# MCU.net
KiCad netlist of a schematic drawn in Altium Designer
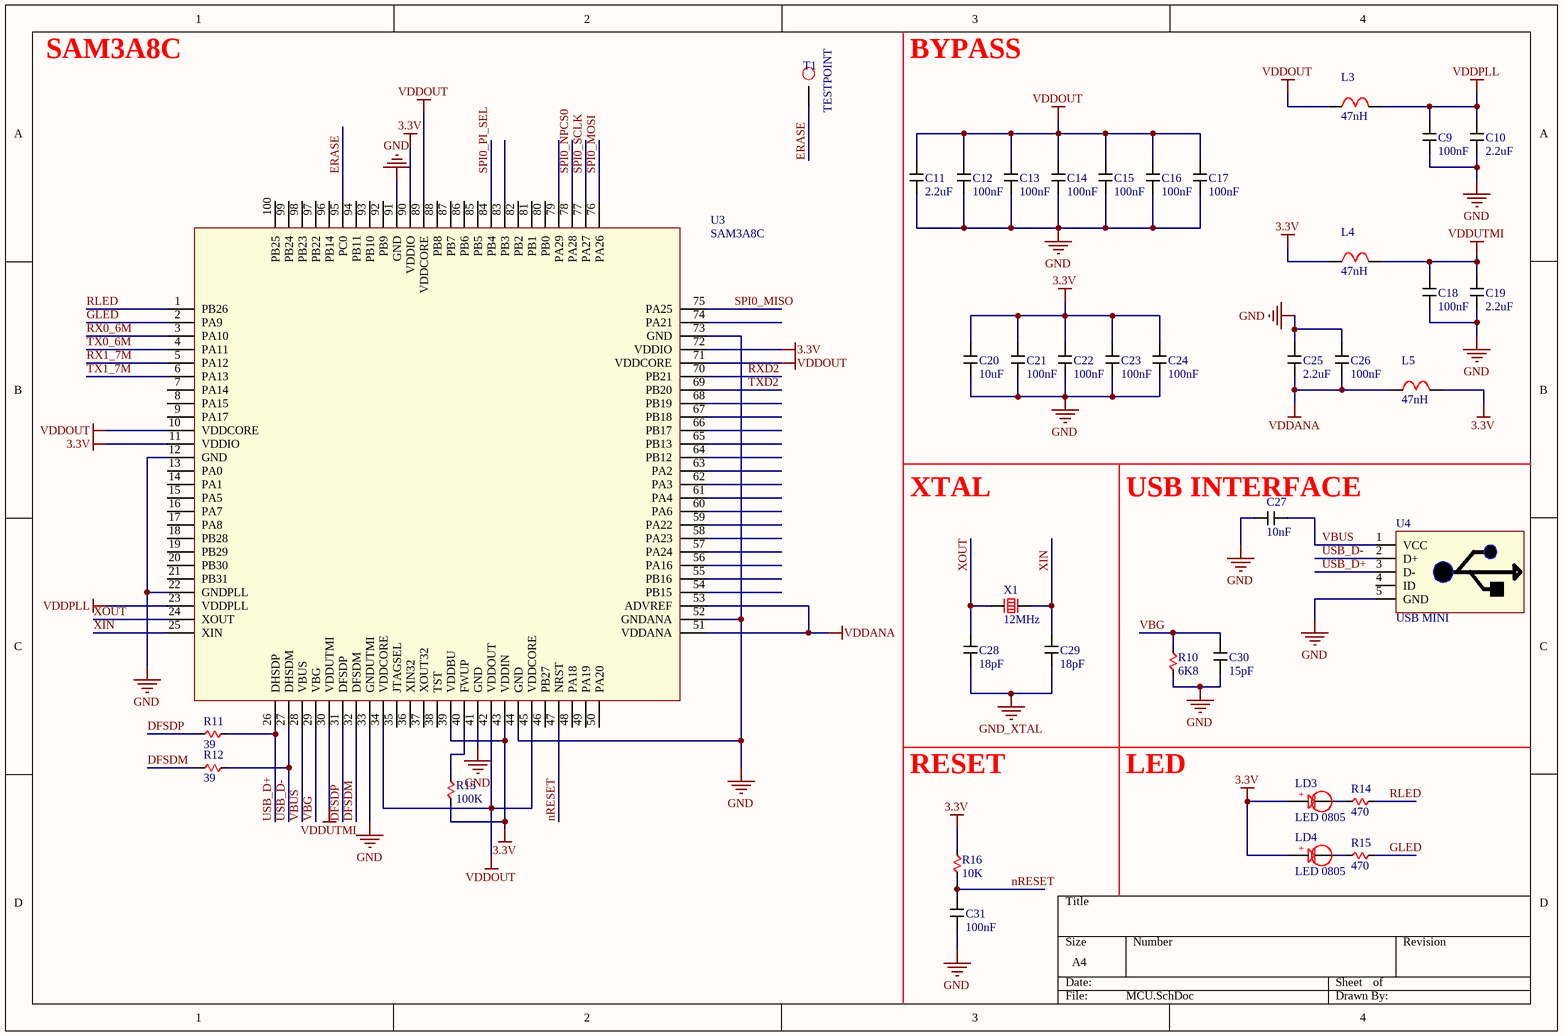
[diagram p0: MCU.SchDoc]

(export (version "E")
  (design (tool "Eeschema 10.0.6"))
  (components
    (comp (ref "C9") (value "100nF") (footprint "C 0805") (libsource (lib "SkyWar") (part "C 0805")))
    (comp (ref "C10") (value "2.2uF") (footprint "C 0805") (libsource (lib "SkyWar") (part "C 0805")))
    (comp (ref "C11") (value "2.2uF") (footprint "C 0805") (libsource (lib "SkyWar") (part "C 0805")))
    (comp (ref "C12") (value "100nF") (footprint "C 0805") (libsource (lib "SkyWar") (part "C 0805")))
    (comp (ref "C13") (value "100nF") (footprint "C 0805") (libsource (lib "SkyWar") (part "C 0805")))
    (comp (ref "C14") (value "100nF") (footprint "C 0805") (libsource (lib "SkyWar") (part "C 0805")))
    (comp (ref "C15") (value "100nF") (footprint "C 0805") (libsource (lib "SkyWar") (part "C 0805")))
    (comp (ref "C16") (value "100nF") (footprint "C 0805") (libsource (lib "SkyWar") (part "C 0805")))
    (comp (ref "C17") (value "100nF") (footprint "C 0805") (libsource (lib "SkyWar") (part "C 0805")))
    (comp (ref "C18") (value "100nF") (footprint "C 0805") (libsource (lib "SkyWar") (part "C 0805")))
    (comp (ref "C19") (value "2.2uF") (footprint "C 0805") (libsource (lib "SkyWar") (part "C 0805")))
    (comp (ref "C20") (value "10uF") (footprint "C 0805") (libsource (lib "SkyWar") (part "C 0805")))
    (comp (ref "C21") (value "100nF") (footprint "C 0805") (libsource (lib "SkyWar") (part "C 0805")))
    (comp (ref "C22") (value "100nF") (footprint "C 0805") (libsource (lib "SkyWar") (part "C 0805")))
    (comp (ref "C23") (value "100nF") (footprint "C 0805") (libsource (lib "SkyWar") (part "C 0805")))
    (comp (ref "C24") (value "100nF") (footprint "C 0805") (libsource (lib "SkyWar") (part "C 0805")))
    (comp (ref "C25") (value "2.2uF") (footprint "C 0805") (libsource (lib "SkyWar") (part "C 0805")))
    (comp (ref "C26") (value "100nF") (footprint "C 0805") (libsource (lib "SkyWar") (part "C 0805")))
    (comp (ref "C27") (value "10nF") (footprint "C 0805") (libsource (lib "SkyWar") (part "C 0805")))
    (comp (ref "C28") (value "18pF") (footprint "C 0805") (libsource (lib "SkyWar") (part "C 0805")))
    (comp (ref "C29") (value "18pF") (footprint "C 0805") (libsource (lib "SkyWar") (part "C 0805")))
    (comp (ref "C30") (value "15pF") (footprint "C 0805") (libsource (lib "SkyWar") (part "C 0805")))
    (comp (ref "C31") (value "100nF") (footprint "C 0805") (libsource (lib "SkyWar") (part "C 0805")))
    (comp (ref "L3") (value "47nH") (footprint "L 0805") (libsource (lib "SkyWar") (part "L 0805")))
    (comp (ref "L4") (value "47nH") (footprint "L 0805") (libsource (lib "SkyWar") (part "L 0805")))
    (comp (ref "L5") (value "47nH") (footprint "L 0805") (libsource (lib "SkyWar") (part "L 0805")))
    (comp (ref "LD3") (value "LED 0805") (footprint "LED 0805") (libsource (lib "SkyWar") (part "LED 0805")))
    (comp (ref "LD4") (value "LED 0805") (footprint "LED 0805") (libsource (lib "SkyWar") (part "LED 0805")))
    (comp (ref "R10") (value "6K8") (footprint "R 0805") (libsource (lib "SkyWar") (part "R 0805")))
    (comp (ref "R11") (value "39") (footprint "R 0805") (libsource (lib "SkyWar") (part "R 0805")))
    (comp (ref "R12") (value "39") (footprint "R 0805") (libsource (lib "SkyWar") (part "R 0805")))
    (comp (ref "R13") (value "100K") (footprint "R 0805") (libsource (lib "SkyWar") (part "R 0805")))
    (comp (ref "R14") (value "470") (footprint "R 0805") (libsource (lib "SkyWar") (part "R 0805")))
    (comp (ref "R15") (value "470") (footprint "R 0805") (libsource (lib "SkyWar") (part "R 0805")))
    (comp (ref "R16") (value "10K") (footprint "R 0805") (libsource (lib "SkyWar") (part "R 0805")))
    (comp (ref "T1")
      (value "TESTPOINT")
      (footprint "TEST_POINT")
      (libsource (lib "SkyWar") (part "TEST_POINT"))
    )
    (comp (ref "U3") (value "SAM3A8C") (footprint "SAM3A8C") (libsource (lib "SkyWar") (part "SAM3A8C")))
    (comp (ref "U4")
      (value "USB MINI")
      (footprint "USB MINI DIP")
      (libsource (lib "SkyWar") (part "USB TYPE B"))
    )
    (comp (ref "X1") (value "12MHz") (footprint "XTAL") (libsource (lib "SkyWar") (part "XTAL")))
  )
  (nets
    (net (code "1") (name "/DFSDM") (class "Default")
      (node (ref "R12") (pin "1") (pinfunction "0_1") (pintype "passive"))
      (node (ref "U3") (pin "32") (pinfunction "DFSDM_32") (pintype "passive"))
    )
    (net (code "2") (name "/DFSDP") (class "Default")
      (node (ref "R11") (pin "1") (pinfunction "0_1") (pintype "passive"))
      (node (ref "U3") (pin "31") (pinfunction "DFSDP_31") (pintype "passive"))
    )
    (net (code "3") (name "/ERASE") (class "Default")
      (node (ref "T1") (pin "1") (pintype "passive"))
      (node (ref "U3") (pin "95") (pinfunction "PC0_95") (pintype "passive"))
    )
    (net (code "4") (name "/GLED") (class "Default")
      (node (ref "R15") (pin "1") (pinfunction "0_1") (pintype "passive"))
      (node (ref "U3") (pin "2") (pinfunction "PA9_2") (pintype "passive"))
    )
    (net (code "5") (name "/RLED") (class "Default")
      (node (ref "R14") (pin "1") (pinfunction "0_1") (pintype "passive"))
      (node (ref "U3") (pin "1") (pinfunction "PB26_1") (pintype "passive"))
    )
    (net (code "6") (name "/RX0_6M") (class "Default")
      (node (ref "U3") (pin "3") (pinfunction "PA10_3") (pintype "passive"))
    )
    (net (code "7") (name "/RX1_7M") (class "Default")
      (node (ref "U3") (pin "5") (pinfunction "PA12_5") (pintype "passive"))
    )
    (net (code "8") (name "/RXD2") (class "Default")
      (node (ref "U3") (pin "70") (pinfunction "PB21_70") (pintype "passive"))
    )
    (net (code "9") (name "/SPI0_MISO") (class "Default")
      (node (ref "U3") (pin "75") (pinfunction "PA25_75") (pintype "passive"))
    )
    (net (code "10") (name "/SPI0_MOSI") (class "Default")
      (node (ref "U3") (pin "76") (pinfunction "PA26_76") (pintype "passive"))
    )
    (net (code "11") (name "/SPI0_NPCS0") (class "Default")
      (node (ref "U3") (pin "78") (pinfunction "PA28_78") (pintype "passive"))
    )
    (net (code "12") (name "/SPI0_PI_SEL") (class "Default")
      (node (ref "U3") (pin "84") (pinfunction "PB4_84") (pintype "passive"))
    )
    (net (code "13") (name "/SPI0_SCLK") (class "Default")
      (node (ref "U3") (pin "77") (pinfunction "PA27_77") (pintype "passive"))
    )
    (net (code "14") (name "/TX0_6M") (class "Default")
      (node (ref "U3") (pin "4") (pinfunction "PA11_4") (pintype "passive"))
    )
    (net (code "15") (name "/TX1_7M") (class "Default")
      (node (ref "U3") (pin "6") (pinfunction "PA13_6") (pintype "passive"))
    )
    (net (code "16") (name "/TXD2") (class "Default")
      (node (ref "U3") (pin "69") (pinfunction "PB20_69") (pintype "passive"))
    )
    (net (code "17") (name "/USB_D+") (class "Default")
      (node (ref "R11") (pin "2") (pinfunction "1_2") (pintype "passive"))
      (node (ref "U3") (pin "26") (pinfunction "DHSDP_26") (pintype "passive"))
      (node (ref "U4") (pin "3") (pinfunction "D-_3") (pintype "passive"))
    )
    (net (code "18") (name "/USB_D-") (class "Default")
      (node (ref "R12") (pin "2") (pinfunction "1_2") (pintype "passive"))
      (node (ref "U3") (pin "27") (pinfunction "DHSDM_27") (pintype "passive"))
      (node (ref "U4") (pin "2") (pinfunction "D+_2") (pintype "passive"))
    )
    (net (code "19") (name "/VBG") (class "Default")
      (node (ref "C30") (pin "2") (pintype "passive"))
      (node (ref "R10") (pin "2") (pinfunction "1_2") (pintype "passive"))
      (node (ref "U3") (pin "29") (pinfunction "VBG_29") (pintype "passive"))
    )
    (net (code "20") (name "/VBUS") (class "Default")
      (node (ref "C27") (pin "1") (pintype "passive"))
      (node (ref "U3") (pin "28") (pinfunction "VBUS_28") (pintype "passive"))
      (node (ref "U4") (pin "1") (pinfunction "VCC_1") (pintype "passive"))
    )
    (net (code "21") (name "/XIN") (class "Default")
      (node (ref "C29") (pin "2") (pintype "passive"))
      (node (ref "U3") (pin "25") (pinfunction "XIN_25") (pintype "passive"))
      (node (ref "X1") (pin "2") (pinfunction "6_2") (pintype "passive"))
    )
    (net (code "22") (name "/XOUT") (class "Default")
      (node (ref "C28") (pin "2") (pintype "passive"))
      (node (ref "U3") (pin "24") (pinfunction "XOUT_24") (pintype "passive"))
      (node (ref "X1") (pin "1") (pinfunction "5_1") (pintype "passive"))
    )
    (net (code "23") (name "/nRESET") (class "Default")
      (node (ref "C31") (pin "2") (pintype "passive"))
      (node (ref "R16") (pin "1") (pinfunction "0_1") (pintype "passive"))
      (node (ref "U3") (pin "47") (pinfunction "NRST_47") (pintype "passive"))
    )
    (net (code "24") (name "3.3V") (class "Default")
      (node (ref "C20") (pin "2") (pintype "passive"))
      (node (ref "C21") (pin "2") (pintype "passive"))
      (node (ref "C22") (pin "2") (pintype "passive"))
      (node (ref "C23") (pin "2") (pintype "passive"))
      (node (ref "C24") (pin "2") (pintype "passive"))
      (node (ref "L4") (pin "1") (pintype "passive"))
      (node (ref "L5") (pin "1") (pintype "passive"))
      (node (ref "LD3") (pin "1") (pinfunction "3_1") (pintype "passive"))
      (node (ref "LD4") (pin "1") (pinfunction "3_1") (pintype "passive"))
      (node (ref "R13") (pin "1") (pinfunction "0_1") (pintype "passive"))
      (node (ref "R16") (pin "2") (pinfunction "1_2") (pintype "passive"))
      (node (ref "U3") (pin "11") (pinfunction "VDDIO_11") (pintype "passive"))
      (node (ref "U3") (pin "39") (pinfunction "VDDBU_39") (pintype "passive"))
      (node (ref "U3") (pin "43") (pinfunction "VDDIN_43") (pintype "passive"))
      (node (ref "U3") (pin "72") (pinfunction "VDDIO_72") (pintype "passive"))
      (node (ref "U3") (pin "90") (pinfunction "VDDIO_90") (pintype "passive"))
    )
    (net (code "25") (name "GND") (class "Default")
      (node (ref "C10") (pin "1") (pintype "passive"))
      (node (ref "C11") (pin "1") (pintype "passive"))
      (node (ref "C12") (pin "1") (pintype "passive"))
      (node (ref "C13") (pin "1") (pintype "passive"))
      (node (ref "C14") (pin "1") (pintype "passive"))
      (node (ref "C15") (pin "1") (pintype "passive"))
      (node (ref "C16") (pin "1") (pintype "passive"))
      (node (ref "C17") (pin "1") (pintype "passive"))
      (node (ref "C18") (pin "1") (pintype "passive"))
      (node (ref "C19") (pin "1") (pintype "passive"))
      (node (ref "C20") (pin "1") (pintype "passive"))
      (node (ref "C21") (pin "1") (pintype "passive"))
      (node (ref "C22") (pin "1") (pintype "passive"))
      (node (ref "C23") (pin "1") (pintype "passive"))
      (node (ref "C24") (pin "1") (pintype "passive"))
      (node (ref "C25") (pin "1") (pintype "passive"))
      (node (ref "C26") (pin "1") (pintype "passive"))
      (node (ref "C27") (pin "2") (pintype "passive"))
      (node (ref "C30") (pin "1") (pintype "passive"))
      (node (ref "C31") (pin "1") (pintype "passive"))
      (node (ref "C9") (pin "1") (pintype "passive"))
      (node (ref "R10") (pin "1") (pinfunction "0_1") (pintype "passive"))
      (node (ref "U3") (pin "12") (pinfunction "GND_12") (pintype "passive"))
      (node (ref "U3") (pin "22") (pinfunction "GNDPLL_22") (pintype "passive"))
      (node (ref "U3") (pin "33") (pinfunction "GNDUTMI_33") (pintype "passive"))
      (node (ref "U3") (pin "41") (pinfunction "GND_41") (pintype "passive"))
      (node (ref "U3") (pin "44") (pinfunction "GND_44") (pintype "passive"))
      (node (ref "U3") (pin "52") (pinfunction "GNDANA_52") (pintype "passive"))
      (node (ref "U3") (pin "73") (pinfunction "GND_73") (pintype "passive"))
      (node (ref "U3") (pin "91") (pinfunction "GND_91") (pintype "passive"))
      (node (ref "U4") (pin "5") (pinfunction "GND_5") (pintype "passive"))
    )
    (net (code "26") (name "GND_XTAL") (class "Default")
      (node (ref "C28") (pin "1") (pintype "passive"))
      (node (ref "C29") (pin "1") (pintype "passive"))
    )
    (net (code "27") (name "Net-(LD3-4)") (class "Default")
      (node (ref "LD3") (pin "2") (pinfunction "4_2") (pintype "passive"))
      (node (ref "R14") (pin "2") (pinfunction "1_2") (pintype "passive"))
    )
    (net (code "28") (name "Net-(LD4-4)") (class "Default")
      (node (ref "LD4") (pin "2") (pinfunction "4_2") (pintype "passive"))
      (node (ref "R15") (pin "2") (pinfunction "1_2") (pintype "passive"))
    )
    (net (code "29") (name "Net-(R13-1)") (class "Default")
      (node (ref "R13") (pin "2") (pinfunction "1_2") (pintype "passive"))
      (node (ref "U3") (pin "40") (pinfunction "FWUP_40") (pintype "passive"))
    )
    (net (code "30") (name "VDDANA") (class "Default")
      (node (ref "C25") (pin "2") (pintype "passive"))
      (node (ref "C26") (pin "2") (pintype "passive"))
      (node (ref "L5") (pin "2") (pintype "passive"))
      (node (ref "U3") (pin "51") (pinfunction "VDDANA_51") (pintype "passive"))
      (node (ref "U3") (pin "53") (pinfunction "ADVREF_53") (pintype "passive"))
    )
    (net (code "31") (name "VDDOUT") (class "Default")
      (node (ref "C11") (pin "2") (pintype "passive"))
      (node (ref "C12") (pin "2") (pintype "passive"))
      (node (ref "C13") (pin "2") (pintype "passive"))
      (node (ref "C14") (pin "2") (pintype "passive"))
      (node (ref "C15") (pin "2") (pintype "passive"))
      (node (ref "C16") (pin "2") (pintype "passive"))
      (node (ref "C17") (pin "2") (pintype "passive"))
      (node (ref "L3") (pin "1") (pintype "passive"))
      (node (ref "U3") (pin "10") (pinfunction "VDDCORE_10") (pintype "passive"))
      (node (ref "U3") (pin "34") (pinfunction "VDDCORE_34") (pintype "passive"))
      (node (ref "U3") (pin "42") (pinfunction "VDDOUT_42") (pintype "passive"))
      (node (ref "U3") (pin "45") (pinfunction "VDDCORE_45") (pintype "passive"))
      (node (ref "U3") (pin "71") (pinfunction "VDDCORE_71") (pintype "passive"))
      (node (ref "U3") (pin "89") (pinfunction "VDDCORE_89") (pintype "passive"))
    )
    (net (code "32") (name "VDDPLL") (class "Default")
      (node (ref "C10") (pin "2") (pintype "passive"))
      (node (ref "C9") (pin "2") (pintype "passive"))
      (node (ref "L3") (pin "2") (pintype "passive"))
      (node (ref "U3") (pin "23") (pinfunction "VDDPLL_23") (pintype "passive"))
    )
    (net (code "33") (name "VDDUTMI") (class "Default")
      (node (ref "C18") (pin "2") (pintype "passive"))
      (node (ref "C19") (pin "2") (pintype "passive"))
      (node (ref "L4") (pin "2") (pintype "passive"))
      (node (ref "U3") (pin "30") (pinfunction "VDDUTMI_30") (pintype "passive"))
    )
    (net (code "34") (name "unconnected-(U3-JTAGSEL-Pad35)") (class "Default")
      (node (ref "U3") (pin "35") (pinfunction "JTAGSEL_35") (pintype "passive"))
    )
    (net (code "35") (name "unconnected-(U3-PA0-Pad13)") (class "Default")
      (node (ref "U3") (pin "13") (pinfunction "PA0_13") (pintype "passive"))
    )
    (net (code "36") (name "unconnected-(U3-PA1-Pad14)") (class "Default")
      (node (ref "U3") (pin "14") (pinfunction "PA1_14") (pintype "passive"))
    )
    (net (code "37") (name "unconnected-(U3-PA2-Pad63)") (class "Default")
      (node (ref "U3") (pin "63") (pinfunction "PA2_63") (pintype "passive"))
    )
    (net (code "38") (name "unconnected-(U3-PA3-Pad62)") (class "Default")
      (node (ref "U3") (pin "62") (pinfunction "PA3_62") (pintype "passive"))
    )
    (net (code "39") (name "unconnected-(U3-PA4-Pad61)") (class "Default")
      (node (ref "U3") (pin "61") (pinfunction "PA4_61") (pintype "passive"))
    )
    (net (code "40") (name "unconnected-(U3-PA5-Pad15)") (class "Default")
      (node (ref "U3") (pin "15") (pinfunction "PA5_15") (pintype "passive"))
    )
    (net (code "41") (name "unconnected-(U3-PA6-Pad60)") (class "Default")
      (node (ref "U3") (pin "60") (pinfunction "PA6_60") (pintype "passive"))
    )
    (net (code "42") (name "unconnected-(U3-PA7-Pad16)") (class "Default")
      (node (ref "U3") (pin "16") (pinfunction "PA7_16") (pintype "passive"))
    )
    (net (code "43") (name "unconnected-(U3-PA8-Pad17)") (class "Default")
      (node (ref "U3") (pin "17") (pinfunction "PA8_17") (pintype "passive"))
    )
    (net (code "44") (name "unconnected-(U3-PA14-Pad7)") (class "Default")
      (node (ref "U3") (pin "7") (pinfunction "PA14_7") (pintype "passive"))
    )
    (net (code "45") (name "unconnected-(U3-PA15-Pad8)") (class "Default")
      (node (ref "U3") (pin "8") (pinfunction "PA15_8") (pintype "passive"))
    )
    (net (code "46") (name "unconnected-(U3-PA16-Pad56)") (class "Default")
      (node (ref "U3") (pin "56") (pinfunction "PA16_56") (pintype "passive"))
    )
    (net (code "47") (name "unconnected-(U3-PA17-Pad9)") (class "Default")
      (node (ref "U3") (pin "9") (pinfunction "PA17_9") (pintype "passive"))
    )
    (net (code "48") (name "unconnected-(U3-PA18-Pad48)") (class "Default")
      (node (ref "U3") (pin "48") (pinfunction "PA18_48") (pintype "passive"))
    )
    (net (code "49") (name "unconnected-(U3-PA19-Pad49)") (class "Default")
      (node (ref "U3") (pin "49") (pinfunction "PA19_49") (pintype "passive"))
    )
    (net (code "50") (name "unconnected-(U3-PA20-Pad50)") (class "Default")
      (node (ref "U3") (pin "50") (pinfunction "PA20_50") (pintype "passive"))
    )
    (net (code "51") (name "unconnected-(U3-PA21-Pad74)") (class "Default")
      (node (ref "U3") (pin "74") (pinfunction "PA21_74") (pintype "passive"))
    )
    (net (code "52") (name "unconnected-(U3-PA22-Pad59)") (class "Default")
      (node (ref "U3") (pin "59") (pinfunction "PA22_59") (pintype "passive"))
    )
    (net (code "53") (name "unconnected-(U3-PA23-Pad58)") (class "Default")
      (node (ref "U3") (pin "58") (pinfunction "PA23_58") (pintype "passive"))
    )
    (net (code "54") (name "unconnected-(U3-PA24-Pad57)") (class "Default")
      (node (ref "U3") (pin "57") (pinfunction "PA24_57") (pintype "passive"))
    )
    (net (code "55") (name "unconnected-(U3-PA29-Pad79)") (class "Default")
      (node (ref "U3") (pin "79") (pinfunction "PA29_79") (pintype "passive"))
    )
    (net (code "56") (name "unconnected-(U3-PB0-Pad80)") (class "Default")
      (node (ref "U3") (pin "80") (pinfunction "PB0_80") (pintype "passive"))
    )
    (net (code "57") (name "unconnected-(U3-PB1-Pad81)") (class "Default")
      (node (ref "U3") (pin "81") (pinfunction "PB1_81") (pintype "passive"))
    )
    (net (code "58") (name "unconnected-(U3-PB2-Pad82)") (class "Default")
      (node (ref "U3") (pin "82") (pinfunction "PB2_82") (pintype "passive"))
    )
    (net (code "59") (name "unconnected-(U3-PB3-Pad83)") (class "Default")
      (node (ref "U3") (pin "83") (pinfunction "PB3_83") (pintype "passive"))
    )
    (net (code "60") (name "unconnected-(U3-PB5-Pad85)") (class "Default")
      (node (ref "U3") (pin "85") (pinfunction "PB5_85") (pintype "passive"))
    )
    (net (code "61") (name "unconnected-(U3-PB6-Pad86)") (class "Default")
      (node (ref "U3") (pin "86") (pinfunction "PB6_86") (pintype "passive"))
    )
    (net (code "62") (name "unconnected-(U3-PB7-Pad87)") (class "Default")
      (node (ref "U3") (pin "87") (pinfunction "PB7_87") (pintype "passive"))
    )
    (net (code "63") (name "unconnected-(U3-PB8-Pad88)") (class "Default")
      (node (ref "U3") (pin "88") (pinfunction "PB8_88") (pintype "passive"))
    )
    (net (code "64") (name "unconnected-(U3-PB9-Pad92)") (class "Default")
      (node (ref "U3") (pin "92") (pinfunction "PB9_92") (pintype "passive"))
    )
    (net (code "65") (name "unconnected-(U3-PB10-Pad93)") (class "Default")
      (node (ref "U3") (pin "93") (pinfunction "PB10_93") (pintype "passive"))
    )
    (net (code "66") (name "unconnected-(U3-PB11-Pad94)") (class "Default")
      (node (ref "U3") (pin "94") (pinfunction "PB11_94") (pintype "passive"))
    )
    (net (code "67") (name "unconnected-(U3-PB12-Pad64)") (class "Default")
      (node (ref "U3") (pin "64") (pinfunction "PB12_64") (pintype "passive"))
    )
    (net (code "68") (name "unconnected-(U3-PB13-Pad65)") (class "Default")
      (node (ref "U3") (pin "65") (pinfunction "PB13_65") (pintype "passive"))
    )
    (net (code "69") (name "unconnected-(U3-PB14-Pad96)") (class "Default")
      (node (ref "U3") (pin "96") (pinfunction "PB14_96") (pintype "passive"))
    )
    (net (code "70") (name "unconnected-(U3-PB15-Pad54)") (class "Default")
      (node (ref "U3") (pin "54") (pinfunction "PB15_54") (pintype "passive"))
    )
    (net (code "71") (name "unconnected-(U3-PB16-Pad55)") (class "Default")
      (node (ref "U3") (pin "55") (pinfunction "PB16_55") (pintype "passive"))
    )
    (net (code "72") (name "unconnected-(U3-PB17-Pad66)") (class "Default")
      (node (ref "U3") (pin "66") (pinfunction "PB17_66") (pintype "passive"))
    )
    (net (code "73") (name "unconnected-(U3-PB18-Pad67)") (class "Default")
      (node (ref "U3") (pin "67") (pinfunction "PB18_67") (pintype "passive"))
    )
    (net (code "74") (name "unconnected-(U3-PB19-Pad68)") (class "Default")
      (node (ref "U3") (pin "68") (pinfunction "PB19_68") (pintype "passive"))
    )
    (net (code "75") (name "unconnected-(U3-PB22-Pad97)") (class "Default")
      (node (ref "U3") (pin "97") (pinfunction "PB22_97") (pintype "passive"))
    )
    (net (code "76") (name "unconnected-(U3-PB23-Pad98)") (class "Default")
      (node (ref "U3") (pin "98") (pinfunction "PB23_98") (pintype "passive"))
    )
    (net (code "77") (name "unconnected-(U3-PB24-Pad99)") (class "Default")
      (node (ref "U3") (pin "99") (pinfunction "PB24_99") (pintype "passive"))
    )
    (net (code "78") (name "unconnected-(U3-PB25-Pad100)") (class "Default")
      (node (ref "U3") (pin "100") (pinfunction "PB25_100") (pintype "passive"))
    )
    (net (code "79") (name "unconnected-(U3-PB27-Pad46)") (class "Default")
      (node (ref "U3") (pin "46") (pinfunction "PB27_46") (pintype "passive"))
    )
    (net (code "80") (name "unconnected-(U3-PB28-Pad18)") (class "Default")
      (node (ref "U3") (pin "18") (pinfunction "PB28_18") (pintype "passive"))
    )
    (net (code "81") (name "unconnected-(U3-PB29-Pad19)") (class "Default")
      (node (ref "U3") (pin "19") (pinfunction "PB29_19") (pintype "passive"))
    )
    (net (code "82") (name "unconnected-(U3-PB30-Pad20)") (class "Default")
      (node (ref "U3") (pin "20") (pinfunction "PB30_20") (pintype "passive"))
    )
    (net (code "83") (name "unconnected-(U3-PB31-Pad21)") (class "Default")
      (node (ref "U3") (pin "21") (pinfunction "PB31_21") (pintype "passive"))
    )
    (net (code "84") (name "unconnected-(U3-TST-Pad38)") (class "Default")
      (node (ref "U3") (pin "38") (pinfunction "TST_38") (pintype "passive"))
    )
    (net (code "85") (name "unconnected-(U3-XIN32-Pad36)") (class "Default")
      (node (ref "U3") (pin "36") (pinfunction "XIN32_36") (pintype "passive"))
    )
    (net (code "86") (name "unconnected-(U3-XOUT32-Pad37)") (class "Default")
      (node (ref "U3") (pin "37") (pinfunction "XOUT32_37") (pintype "passive"))
    )
    (net (code "87") (name "unconnected-(U4-ID-Pad4)") (class "Default")
      (node (ref "U4") (pin "4") (pinfunction "ID_4") (pintype "passive"))
    )
  )
)
